# Encoder_Sheet4.net
KiCad netlist of a schematic drawn in Altium Designer
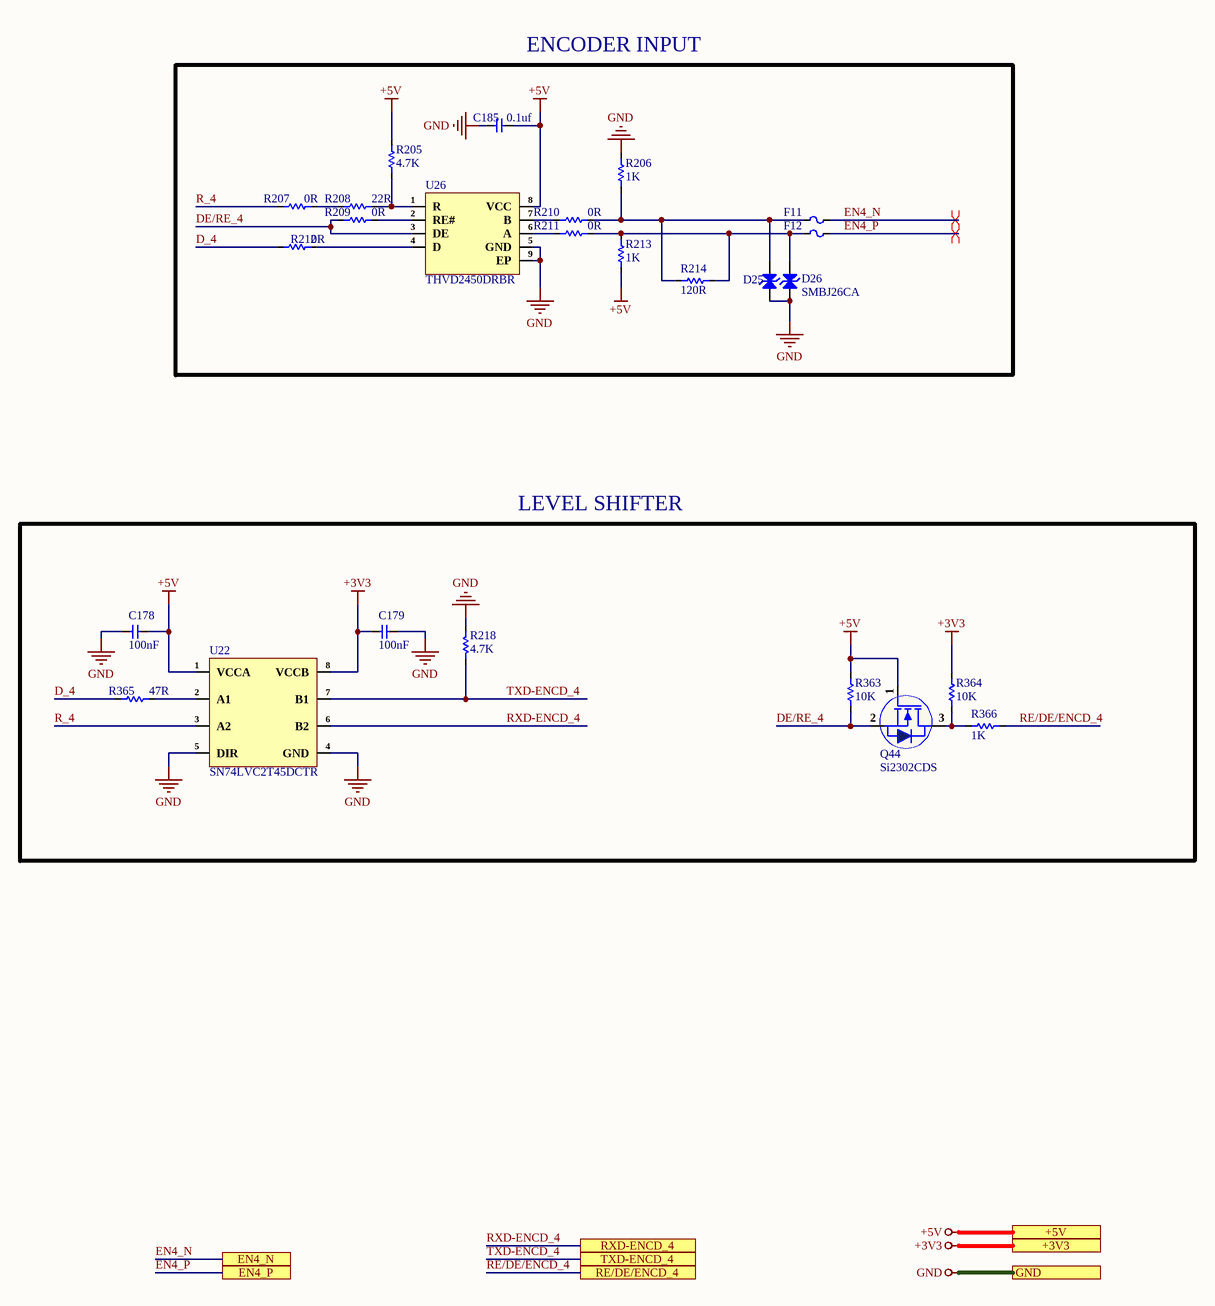
[diagram p0: Encoder_Sheet4.SchDoc]

(export (version "E")
  (design (tool "Eeschema 10.0.6"))
  (components
    (comp (ref "C178")
      (value "100nF")
      (footprint "cap-0402")
      (description "CAP CER 0.1UF 50V X7R 0402")
      (fields
        (field (name "MANUFACTURER") "TDK")
        (field (name "MANUFACTURER PART NUMBER") "C1005X7R1H104KT000F")
      )
      (libsource (lib "eSpark Libraries") (part "C1005X7R1H104KT000F"))
    )
    (comp (ref "C179")
      (value "100nF")
      (footprint "cap-0402")
      (description "CAP CER 0.1UF 50V X7R 0402")
      (fields
        (field (name "MANUFACTURER") "TDK")
        (field (name "MANUFACTURER PART NUMBER") "C1005X7R1H104KT000F")
      )
      (libsource (lib "eSpark Libraries") (part "C1005X7R1H104KT000F"))
    )
    (comp (ref "C185")
      (value "0.1uf")
      (footprint "Cap-0402")
      (description "CAP CER 0.1UF 100V X5R 0402")
      (fields
        (field (name "MANUFACTURER") "Murata")
        (field (name "MANUFACTURER PART NUMBER") "GRM155R62A104KE14D")
      )
      (libsource (lib "eSpark Libraries") (part "GRM155R62A104KE14D"))
    )
    (comp (ref "D25")
      (value "SMBJ26CA")
      (footprint "SMB Bi Directional")
      (description "SMB(DO-214AA) TVS ROHS")
      (fields (field (name "MANUFACTURER") "MSKSEMI") (field (name "LCSC PART NUMBER") "C5331111"))
      (libsource (lib "eSpark Libraries") (part "SMBJ26CA"))
    )
    (comp (ref "D26")
      (value "SMBJ26CA")
      (footprint "SMB Bi Directional")
      (description "SMB(DO-214AA) TVS ROHS")
      (fields (field (name "MANUFACTURER") "MSKSEMI") (field (name "LCSC PART NUMBER") "C5331111"))
      (libsource (lib "eSpark Libraries") (part "SMBJ26CA"))
    )
    (comp (ref "F11")
      (value "SMD0805P020TF")
      (footprint "Fuse-0805")
      (description "9V 200mA 100A 500mA 0805 Resettable Fuses ROHS")
      (fields (field (name "MANUFACTURER") "RUILON") (field (name "LCSC PART NUMBER") "C20976"))
      (libsource (lib "eSpark_centralized_Library(2022)") (part "SMD0805P020TF"))
    )
    (comp (ref "F12")
      (value "SMD0805P020TF")
      (footprint "Fuse-0805")
      (description "9V 200mA 100A 500mA 0805 Resettable Fuses ROHS")
      (fields (field (name "MANUFACTURER") "RUILON") (field (name "LCSC PART NUMBER") "C20976"))
      (libsource (lib "eSpark_centralized_Library(2022)") (part "SMD0805P020TF"))
    )
    (comp (ref "Q44")
      (value "Si2302CDS")
      (footprint "Sot-23")
      (description "N-CHANNEL 20-V (D-S) MOSFET")
      (fields
        (field (name "MANUFACTURER") "TECH PUBLIC")
        (field (name "MANUFACTURER PART NUMBER") "SI2302CDS")
      )
      (libsource (lib "eSpark_centralized_Library(2022)") (part "Si2302CDS"))
    )
    (comp (ref "R205")
      (value "4.7K")
      (footprint "Res-0402")
      (description "RES 4.7K OHM 1% 1/16W 0402")
      (fields
        (field (name "MANUFACTURER") "Yageo")
        (field (name "MANUFACTURER PART NUMBER") "RC0402FR-074K7L")
      )
      (libsource (lib "eSpark Libraries") (part "RC0402FR-074K7L"))
    )
    (comp (ref "R206")
      (value "1K")
      (footprint "Res-0402")
      (description "RES 1K OHM 1% 1/16W 0402")
      (fields
        (field (name "MANUFACTURER") "Yageo")
        (field (name "MANUFACTURER PART NUMBER") "RC0402FR-071KL")
      )
      (libsource (lib "eSpark Libraries") (part "RC0402FR-071KL"))
    )
    (comp (ref "R207")
      (value "0R")
      (footprint "Res-0603")
      (description "RES 0 OHM JUMPER 1/10W 0603")
      (fields
        (field (name "MANUFACTURER") "Yageo")
        (field (name "MANUFACTURER PART NUMBER") "RC0603JR-070RL")
      )
      (libsource (lib "eSpark Libraries") (part "RC0603JR-070RL"))
    )
    (comp (ref "R208")
      (value "22R")
      (footprint "Res-0402")
      (description "RES 22 OHM 1% 1/16W 0402")
      (fields
        (field (name "MANUFACTURER") "Yageo")
        (field (name "MANUFACTURER PART NUMBER") "RC0402FR-0722RL")
      )
      (libsource (lib "eSpark Libraries") (part "RC0402FR-0722RL"))
    )
    (comp (ref "R209")
      (value "0R")
      (footprint "Res-0603")
      (description "RES 0 OHM JUMPER 1/10W 0603")
      (fields
        (field (name "MANUFACTURER") "Yageo")
        (field (name "MANUFACTURER PART NUMBER") "RC0603JR-070RL")
      )
      (libsource (lib "eSpark Libraries") (part "RC0603JR-070RL"))
    )
    (comp (ref "R210")
      (value "0R")
      (footprint "Res-0603")
      (description "RES 0 OHM JUMPER 1/10W 0603")
      (fields
        (field (name "MANUFACTURER") "Yageo")
        (field (name "MANUFACTURER PART NUMBER") "RC0603JR-070RL")
      )
      (libsource (lib "eSpark Libraries") (part "RC0603JR-070RL"))
    )
    (comp (ref "R211")
      (value "0R")
      (footprint "Res-0603")
      (description "RES 0 OHM JUMPER 1/10W 0603")
      (fields
        (field (name "MANUFACTURER") "Yageo")
        (field (name "MANUFACTURER PART NUMBER") "RC0603JR-070RL")
      )
      (libsource (lib "eSpark Libraries") (part "RC0603JR-070RL"))
    )
    (comp (ref "R212")
      (value "0R")
      (footprint "Res-0603")
      (description "RES 0 OHM JUMPER 1/10W 0603")
      (fields
        (field (name "MANUFACTURER") "Yageo")
        (field (name "MANUFACTURER PART NUMBER") "RC0603JR-070RL")
      )
      (libsource (lib "eSpark Libraries") (part "RC0603JR-070RL"))
    )
    (comp (ref "R213")
      (value "1K")
      (footprint "Res-0402")
      (description "RES 1K OHM 1% 1/16W 0402")
      (fields
        (field (name "MANUFACTURER") "Yageo")
        (field (name "MANUFACTURER PART NUMBER") "RC0402FR-071KL")
      )
      (libsource (lib "eSpark Libraries") (part "RC0402FR-071KL"))
    )
    (comp (ref "R214")
      (value "120R")
      (footprint "Res-0402")
      (description "RES 120 OHM 1% 1/16W 0402")
      (fields
        (field (name "MANUFACTURER") "Yageo")
        (field (name "MANUFACTURER PART NUMBER") "RC0402FR-07120RL")
      )
      (libsource (lib "eSpark Libraries") (part "RC0402FR-07120RL"))
    )
    (comp (ref "R218")
      (value "4.7K")
      (footprint "Res-0402")
      (description "RES 4.7K OHM 1% 1/16W 0402")
      (fields
        (field (name "MANUFACTURER") "Yageo")
        (field (name "MANUFACTURER PART NUMBER") "RC0402FR-074K7L")
      )
      (libsource (lib "eSpark Libraries") (part "RC0402FR-074K7L"))
    )
    (comp (ref "R363")
      (value "10K")
      (footprint "Res-0402")
      (description "RES 10K OHM 1% 1/16W 0402")
      (fields
        (field (name "MANUFACTURER") "Yageo")
        (field (name "MANUFACTURER PART NUMBER") "RC0402FR-0710KL")
      )
      (libsource (lib "eSpark_centralized_Library(2022)") (part "RC0402FR-0710KL"))
    )
    (comp (ref "R364")
      (value "10K")
      (footprint "Res-0402")
      (description "RES 10K OHM 1% 1/16W 0402")
      (fields
        (field (name "MANUFACTURER") "Yageo")
        (field (name "MANUFACTURER PART NUMBER") "RC0402FR-0710KL")
      )
      (libsource (lib "eSpark_centralized_Library(2022)") (part "RC0402FR-0710KL"))
    )
    (comp (ref "R365")
      (value "47R")
      (footprint "Res-0402")
      (description "RES 47 OHM 1% 1/16W 0402")
      (fields
        (field (name "MANUFACTURER") "Yageo")
        (field (name "MANUFACTURER PART NUMBER") "RC0402FR-0747RL")
      )
      (libsource (lib "eSpark Libraries") (part "RC0402FR-0747RL"))
    )
    (comp (ref "R366")
      (value "1K")
      (footprint "Res-0603")
      (description "RES SMD 1K OHM 1% 1/10W 0603")
      (fields
        (field (name "MANUFACTURER") "Yageo")
        (field (name "MANUFACTURER PART NUMBER") "RC0603FR-071KL")
      )
      (libsource (lib "eSpark_centralized_Library(2022)") (part "RC0603FR-071KL"))
    )
    (comp (ref "U22")
      (value "SN74LVC2T45DCTR")
      (footprint "MSOP-8")
      (description "IC TRANSLATOR BIDIRECTIONAL SM8")
      (fields (field (name "LCSC PART NUMBER") "C22672") (field (name "MANUFACTURER") "Texas Instruments"))
      (libsource (lib "eSpark Libraries") (part "SN74LVC2T45DCTR"))
    )
    (comp (ref "U26")
      (value "THVD2450DRBR")
      (footprint "SON-8-EP(3x3)")
      (description "IC TRANSCEIVER HALF 1/1 8SON")
      (fields (field (name "MANUFACTURER") "Texas Instruments") (field (name "LCSC PART NUMBER") "C2878080"))
      (libsource (lib "eSpark Libraries") (part "THVD2450DRBR"))
    )
  )
  (nets
    (net (code "1") (name "+3V3") (class "Default")
      (node (ref "C179") (pin "1") (pinfunction "1_1") (pintype "passive"))
      (node (ref "R364") (pin "1") (pinfunction "1_1") (pintype "passive"))
      (node (ref "U22") (pin "8") (pinfunction "VCCB_8") (pintype "passive"))
    )
    (net (code "2") (name "+5V") (class "Default")
      (node (ref "C178") (pin "1") (pinfunction "1_1") (pintype "passive"))
      (node (ref "C185") (pin "2") (pinfunction "2_2") (pintype "passive"))
      (node (ref "Q44") (pin "1") (pinfunction "G_1") (pintype "passive"))
      (node (ref "R205") (pin "2") (pinfunction "2_2") (pintype "passive"))
      (node (ref "R213") (pin "1") (pinfunction "1_1") (pintype "passive"))
      (node (ref "R363") (pin "1") (pinfunction "1_1") (pintype "passive"))
      (node (ref "U22") (pin "1") (pinfunction "VCCA_1") (pintype "passive"))
      (node (ref "U26") (pin "8") (pinfunction "VCC_8") (pintype "passive"))
    )
    (net (code "3") (name "/DE{slash}RE_4") (class "Default")
      (node (ref "Q44") (pin "2") (pinfunction "S_2") (pintype "passive"))
      (node (ref "R209") (pin "1") (pinfunction "1_1") (pintype "passive"))
      (node (ref "R363") (pin "2") (pinfunction "2_2") (pintype "passive"))
      (node (ref "U26") (pin "3") (pinfunction "DE_3") (pintype "passive"))
    )
    (net (code "4") (name "/D_4") (class "Default")
      (node (ref "R212") (pin "1") (pinfunction "1_1") (pintype "passive"))
      (node (ref "R365") (pin "1") (pinfunction "1_1") (pintype "passive"))
    )
    (net (code "5") (name "/EN4_N") (class "Default")
      (node (ref "F11") (pin "2") (pinfunction "2_2") (pintype "passive"))
    )
    (net (code "6") (name "/EN4_P") (class "Default")
      (node (ref "F12") (pin "2") (pinfunction "2_2") (pintype "passive"))
    )
    (net (code "7") (name "/RE{slash}DE{slash}ENCD_4") (class "Default")
      (node (ref "R366") (pin "2") (pinfunction "2_2") (pintype "passive"))
    )
    (net (code "8") (name "/RXD-ENCD_4") (class "Default")
      (node (ref "U22") (pin "6") (pinfunction "B2_6") (pintype "passive"))
    )
    (net (code "9") (name "/R_4") (class "Default")
      (node (ref "R207") (pin "1") (pinfunction "1_1") (pintype "passive"))
      (node (ref "U22") (pin "3") (pinfunction "A2_3") (pintype "passive"))
    )
    (net (code "10") (name "/TXD-ENCD_4") (class "Default")
      (node (ref "R218") (pin "1") (pinfunction "1_1") (pintype "passive"))
      (node (ref "U22") (pin "7") (pinfunction "B1_7") (pintype "passive"))
    )
    (net (code "11") (name "GND") (class "Default")
      (node (ref "C178") (pin "2") (pinfunction "2_2") (pintype "passive"))
      (node (ref "C179") (pin "2") (pinfunction "2_2") (pintype "passive"))
      (node (ref "C185") (pin "1") (pinfunction "1_1") (pintype "passive"))
      (node (ref "D25") (pin "1") (pinfunction "A_1") (pintype "passive"))
      (node (ref "D26") (pin "1") (pinfunction "A_1") (pintype "passive"))
      (node (ref "R206") (pin "2") (pinfunction "2_2") (pintype "passive"))
      (node (ref "R218") (pin "2") (pinfunction "2_2") (pintype "passive"))
      (node (ref "U22") (pin "4") (pinfunction "GND_4") (pintype "passive"))
      (node (ref "U22") (pin "5") (pinfunction "DIR_5") (pintype "passive"))
      (node (ref "U26") (pin "5") (pinfunction "GND_5") (pintype "passive"))
      (node (ref "U26") (pin "9") (pinfunction "EP_9") (pintype "passive"))
    )
    (net (code "12") (name "Net-(D25-K)") (class "Default")
      (node (ref "D25") (pin "2") (pinfunction "K_2") (pintype "passive"))
      (node (ref "F11") (pin "1") (pinfunction "1_1") (pintype "passive"))
      (node (ref "R206") (pin "1") (pinfunction "1_1") (pintype "passive"))
      (node (ref "R210") (pin "2") (pinfunction "2_2") (pintype "passive"))
      (node (ref "R214") (pin "1") (pinfunction "1_1") (pintype "passive"))
    )
    (net (code "13") (name "Net-(D26-K)") (class "Default")
      (node (ref "D26") (pin "2") (pinfunction "K_2") (pintype "passive"))
      (node (ref "F12") (pin "1") (pinfunction "1_1") (pintype "passive"))
      (node (ref "R211") (pin "2") (pinfunction "2_2") (pintype "passive"))
      (node (ref "R213") (pin "2") (pinfunction "2_2") (pintype "passive"))
      (node (ref "R214") (pin "2") (pinfunction "2_2") (pintype "passive"))
    )
    (net (code "14") (name "Net-(Q44-D)") (class "Default")
      (node (ref "Q44") (pin "3") (pinfunction "D_3") (pintype "passive"))
      (node (ref "R364") (pin "2") (pinfunction "2_2") (pintype "passive"))
      (node (ref "R366") (pin "1") (pinfunction "1_1") (pintype "passive"))
    )
    (net (code "15") (name "Net-(R207-Pad2)") (class "Default")
      (node (ref "R207") (pin "2") (pinfunction "2_2") (pintype "passive"))
      (node (ref "R208") (pin "1") (pinfunction "1_1") (pintype "passive"))
    )
    (net (code "16") (name "Net-(U22-A1)") (class "Default")
      (node (ref "R365") (pin "2") (pinfunction "2_2") (pintype "passive"))
      (node (ref "U22") (pin "2") (pinfunction "A1_2") (pintype "passive"))
    )
    (net (code "17") (name "Net-(U26-A)") (class "Default")
      (node (ref "R211") (pin "1") (pinfunction "1_1") (pintype "passive"))
      (node (ref "U26") (pin "6") (pinfunction "A_6") (pintype "passive"))
    )
    (net (code "18") (name "Net-(U26-B)") (class "Default")
      (node (ref "R210") (pin "1") (pinfunction "1_1") (pintype "passive"))
      (node (ref "U26") (pin "7") (pinfunction "B_7") (pintype "passive"))
    )
    (net (code "19") (name "Net-(U26-D)") (class "Default")
      (node (ref "R212") (pin "2") (pinfunction "2_2") (pintype "passive"))
      (node (ref "U26") (pin "4") (pinfunction "D_4") (pintype "passive"))
    )
    (net (code "20") (name "Net-(U26-R)") (class "Default")
      (node (ref "R205") (pin "1") (pinfunction "1_1") (pintype "passive"))
      (node (ref "R208") (pin "2") (pinfunction "2_2") (pintype "passive"))
      (node (ref "U26") (pin "1") (pinfunction "R_1") (pintype "passive"))
    )
    (net (code "21") (name "Net-(U26-RE#)") (class "Default")
      (node (ref "R209") (pin "2") (pinfunction "2_2") (pintype "passive"))
      (node (ref "U26") (pin "2") (pinfunction "RE#_2") (pintype "passive"))
    )
  )
)
